# dual_power_board.net
KiCad netlist of a schematic drawn in EAGLE
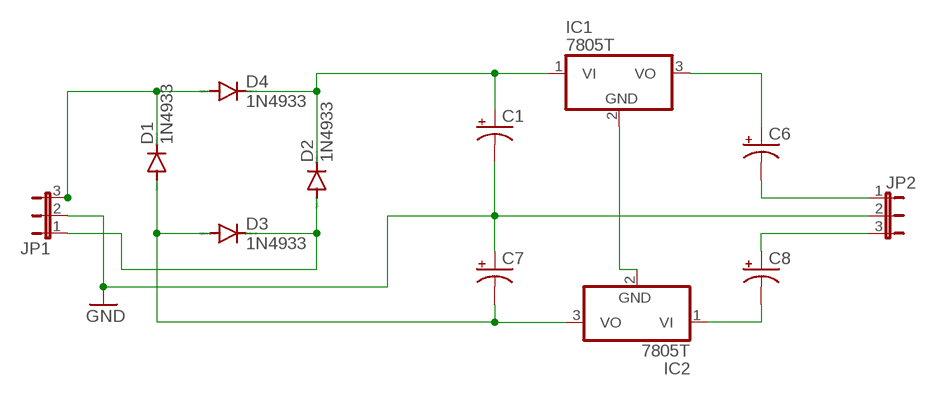
[diagram p0: schematic, sheet 1]

(export (version "E")
  (design (tool "Eeschema 10.0.6"))
  (components
    (comp (ref "C1")
      (value "CPOL-USE5-5")
      (footprint "eagle-import:E5-5")
      (libsource (lib "eagle-import") (part "CPOL-USE5-5"))
    )
    (comp (ref "C6")
      (value "CPOL-USE5-5")
      (footprint "eagle-import:E5-5")
      (libsource (lib "eagle-import") (part "CPOL-USE5-5"))
    )
    (comp (ref "C7")
      (value "CPOL-USE5-5")
      (footprint "eagle-import:E5-5")
      (libsource (lib "eagle-import") (part "CPOL-USE5-5"))
    )
    (comp (ref "C8")
      (value "CPOL-USE5-5")
      (footprint "eagle-import:E5-5")
      (libsource (lib "eagle-import") (part "CPOL-USE5-5"))
    )
    (comp (ref "D1")
      (value "1N4933")
      (footprint "eagle-import:DO41-10")
      (libsource (lib "eagle-import") (part "1N4933"))
    )
    (comp (ref "D2")
      (value "1N4933")
      (footprint "eagle-import:DO41-10")
      (libsource (lib "eagle-import") (part "1N4933"))
    )
    (comp (ref "D3")
      (value "1N4933")
      (footprint "eagle-import:DO41-10")
      (libsource (lib "eagle-import") (part "1N4933"))
    )
    (comp (ref "D4")
      (value "1N4933")
      (footprint "eagle-import:DO41-10")
      (libsource (lib "eagle-import") (part "1N4933"))
    )
    (comp (ref "IC1")
      (value "7805T")
      (footprint "eagle-import:TO220H")
      (libsource (lib "eagle-import") (part "78T05"))
    )
    (comp (ref "IC2")
      (value "7805T")
      (footprint "eagle-import:TO220H")
      (libsource (lib "eagle-import") (part "78T05"))
    )
    (comp (ref "JP1")
      (value "JP2E")
      (footprint "eagle-import:JP2")
      (libsource (lib "eagle-import") (part "JP2E"))
    )
    (comp (ref "JP2")
      (value "JP2E")
      (footprint "eagle-import:JP2")
      (libsource (lib "eagle-import") (part "JP2E"))
    )
  )
  (nets
    (net (code "1") (name "GND") (class "Default")
      (node (ref "C1") (pin "-") (pinfunction "-_-") (pintype "passive"))
      (node (ref "C7") (pin "+") (pinfunction "+_+") (pintype "passive"))
      (node (ref "JP1") (pin "2") (pinfunction "2_2") (pintype "passive"))
      (node (ref "JP2") (pin "2") (pinfunction "2_2") (pintype "passive"))
    )
    (net (code "2") (name "Net-(C6-Pad-)") (class "Default")
      (node (ref "C6") (pin "-") (pinfunction "-_-") (pintype "passive"))
      (node (ref "JP2") (pin "1") (pinfunction "1_1") (pintype "passive"))
    )
    (net (code "3") (name "Net-(C8-Pad+)") (class "Default")
      (node (ref "C8") (pin "+") (pinfunction "+_+") (pintype "passive"))
      (node (ref "JP2") (pin "3") (pinfunction "3_3") (pintype "passive"))
    )
    (net (code "4") (name "Net-(D1-PadC)") (class "Default")
      (node (ref "D1") (pin "C") (pinfunction "C_C") (pintype "passive"))
      (node (ref "D4") (pin "A") (pinfunction "A_A") (pintype "passive"))
      (node (ref "JP1") (pin "3") (pinfunction "3_3") (pintype "passive"))
    )
    (net (code "5") (name "Net-(D2-PadA)") (class "Default")
      (node (ref "D2") (pin "A") (pinfunction "A_A") (pintype "passive"))
      (node (ref "D3") (pin "C") (pinfunction "C_C") (pintype "passive"))
      (node (ref "JP1") (pin "1") (pinfunction "1_1") (pintype "passive"))
    )
    (net (code "6") (name "Net-(IC1-GND)") (class "Default")
      (node (ref "IC1") (pin "2") (pinfunction "GND_2") (pintype "passive"))
      (node (ref "IC2") (pin "2") (pinfunction "GND_2") (pintype "passive"))
    )
    (net (code "7") (name "Net-(IC1-VI)") (class "Default")
      (node (ref "C1") (pin "+") (pinfunction "+_+") (pintype "passive"))
      (node (ref "D2") (pin "C") (pinfunction "C_C") (pintype "passive"))
      (node (ref "D4") (pin "C") (pinfunction "C_C") (pintype "passive"))
      (node (ref "IC1") (pin "1") (pinfunction "VI_1") (pintype "input"))
    )
    (net (code "8") (name "Net-(IC1-VO)") (class "Default")
      (node (ref "C6") (pin "+") (pinfunction "+_+") (pintype "passive"))
      (node (ref "IC1") (pin "3") (pinfunction "VO_3") (pintype "passive"))
    )
    (net (code "9") (name "Net-(IC2-VI)") (class "Default")
      (node (ref "C8") (pin "-") (pinfunction "-_-") (pintype "passive"))
      (node (ref "IC2") (pin "1") (pinfunction "VI_1") (pintype "input"))
    )
    (net (code "10") (name "Net-(IC2-VO)") (class "Default")
      (node (ref "C7") (pin "-") (pinfunction "-_-") (pintype "passive"))
      (node (ref "D1") (pin "A") (pinfunction "A_A") (pintype "passive"))
      (node (ref "D3") (pin "A") (pinfunction "A_A") (pintype "passive"))
      (node (ref "IC2") (pin "3") (pinfunction "VO_3") (pintype "passive"))
    )
  )
)
